# Sheet1.net
KiCad netlist of a schematic drawn in Altium Designer
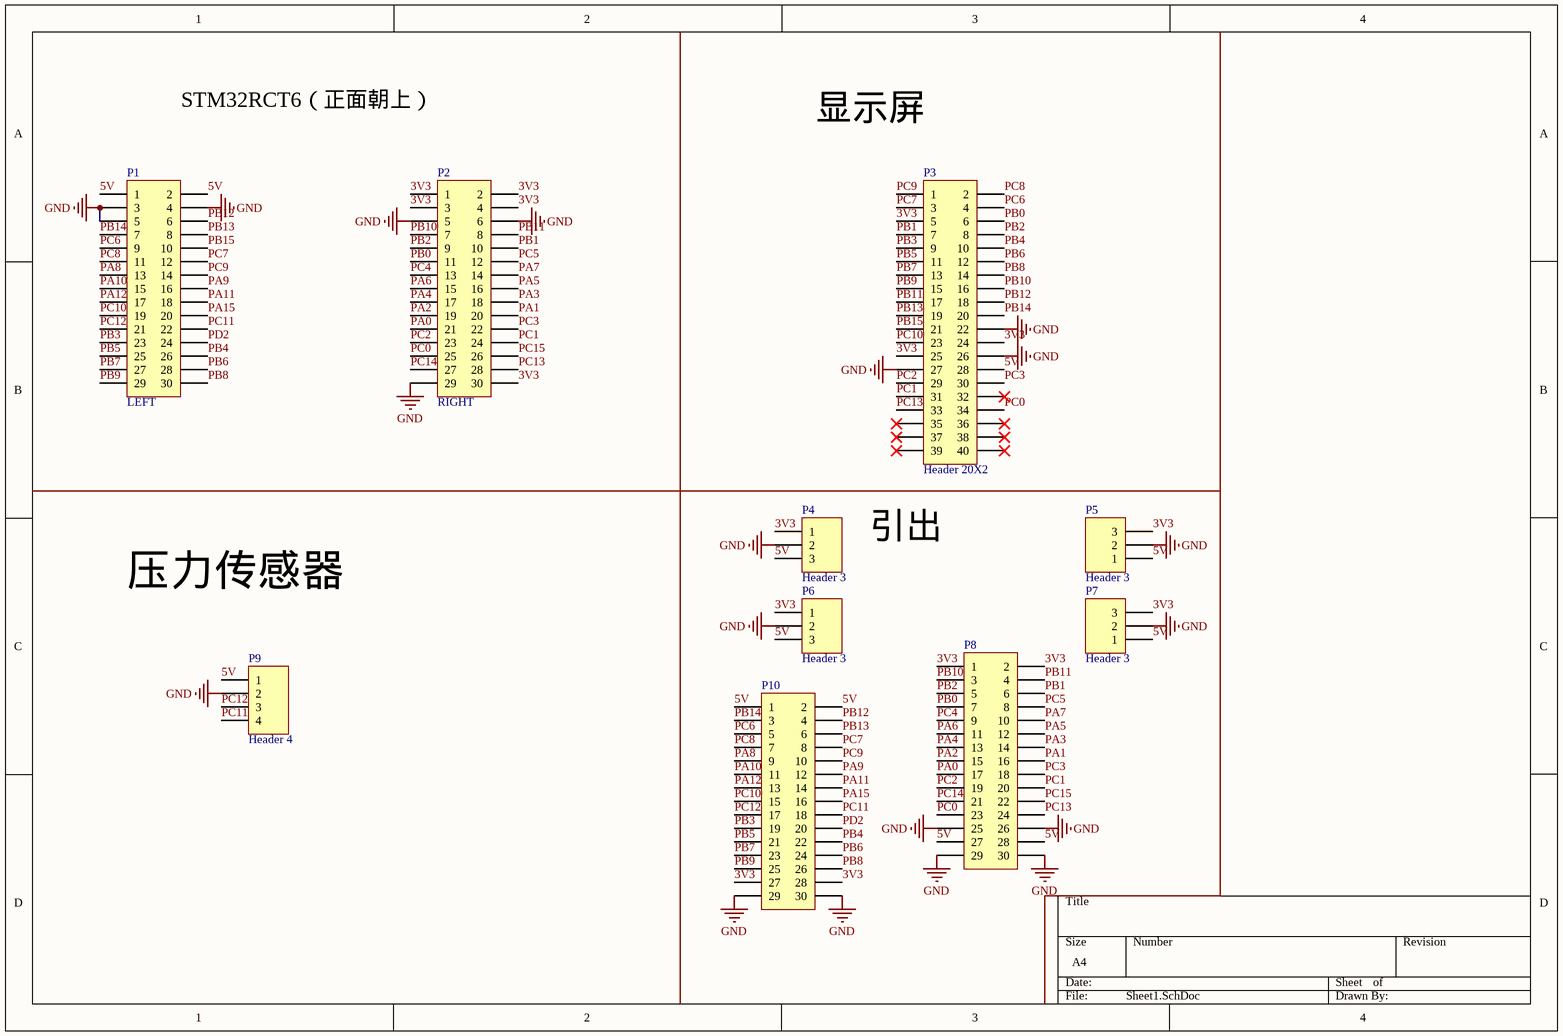
[diagram p0: Sheet1.SchDoc]

(export (version "E")
  (design (tool "Eeschema 10.0.6"))
  (components
    (comp (ref "P1")
      (value "LEFT")
      (footprint "IDE15X2_2.54")
      (description "Header, 15-Pin, Dual row")
      (fields (field (name "PUBLISHER") "Altium Limited"))
      (libsource (lib "Miscellaneous Connectors") (part "Header 15X2"))
    )
    (comp (ref "P2")
      (value "RIGHT")
      (footprint "IDE15X2_2.54")
      (description "Header, 15-Pin, Dual row")
      (fields (field (name "PUBLISHER") "Altium Limited"))
      (libsource (lib "Miscellaneous Connectors") (part "Header 15X2"))
    )
    (comp (ref "P3")
      (value "Header 20X2")
      (footprint "HDR2X20")
      (description "Header, 20-Pin, Dual row")
      (fields (field (name "PUBLISHER") "Altium Limited"))
      (libsource (lib "Miscellaneous Connectors") (part "Header 20X2"))
    )
    (comp (ref "P4")
      (value "Header 3")
      (footprint "HDR1X3")
      (description "Header, 3-Pin")
      (fields (field (name "PUBLISHER") "Altium Limited"))
      (libsource (lib "Miscellaneous Connectors") (part "Header 3"))
    )
    (comp (ref "P5")
      (value "Header 3")
      (footprint "HDR1X3")
      (description "Header, 3-Pin")
      (fields (field (name "PUBLISHER") "Altium Limited"))
      (libsource (lib "") (part "Header 3_1"))
    )
    (comp (ref "P6")
      (value "Header 3")
      (footprint "HDR1X3")
      (description "Header, 3-Pin")
      (fields (field (name "PUBLISHER") "Altium Limited"))
      (libsource (lib "Miscellaneous Connectors") (part "Header 3"))
    )
    (comp (ref "P7")
      (value "Header 3")
      (footprint "HDR1X3")
      (description "Header, 3-Pin")
      (fields (field (name "PUBLISHER") "Altium Limited"))
      (libsource (lib "") (part "Header 3_1"))
    )
    (comp (ref "P8")
      (value "~")
      (footprint "IDE15X2_2.54")
      (description "Header, 15-Pin, Dual row")
      (fields (field (name "PUBLISHER") "Altium Limited"))
      (libsource (lib "Miscellaneous Connectors") (part "Header 15X2"))
    )
    (comp (ref "P9")
      (value "Header 4")
      (footprint "HDR1X4")
      (description "Header, 4-Pin")
      (fields (field (name "PUBLISHER") "Altium Limited"))
      (libsource (lib "Miscellaneous Connectors") (part "Header 4"))
    )
    (comp (ref "P10")
      (value "~")
      (footprint "IDE15X2_2.54")
      (description "Header, 15-Pin, Dual row")
      (fields (field (name "PUBLISHER") "Altium Limited"))
      (libsource (lib "Miscellaneous Connectors") (part "Header 15X2"))
    )
  )
  (nets
    (net (code "1") (name "/3V3") (class "Default")
      (node (ref "P10") (pin "27") (pinfunction "27_27") (pintype "passive"))
      (node (ref "P10") (pin "28") (pinfunction "28_28") (pintype "passive"))
      (node (ref "P2") (pin "1") (pinfunction "1_1") (pintype "passive"))
      (node (ref "P2") (pin "2") (pinfunction "2_2") (pintype "passive"))
      (node (ref "P2") (pin "3") (pinfunction "3_3") (pintype "passive"))
      (node (ref "P2") (pin "30") (pinfunction "30_30") (pintype "passive"))
      (node (ref "P2") (pin "4") (pinfunction "4_4") (pintype "passive"))
      (node (ref "P3") (pin "24") (pinfunction "24_24") (pintype "passive"))
      (node (ref "P3") (pin "25") (pinfunction "25_25") (pintype "passive"))
      (node (ref "P3") (pin "5") (pinfunction "5_5") (pintype "passive"))
      (node (ref "P4") (pin "1") (pinfunction "1_1") (pintype "passive"))
      (node (ref "P5") (pin "3") (pinfunction "3_3") (pintype "passive"))
      (node (ref "P6") (pin "1") (pinfunction "1_1") (pintype "passive"))
      (node (ref "P7") (pin "3") (pinfunction "3_3") (pintype "passive"))
      (node (ref "P8") (pin "1") (pinfunction "1_1") (pintype "passive"))
      (node (ref "P8") (pin "2") (pinfunction "2_2") (pintype "passive"))
    )
    (net (code "2") (name "/5V") (class "Default")
      (node (ref "P1") (pin "1") (pinfunction "1_1") (pintype "passive"))
      (node (ref "P1") (pin "2") (pinfunction "2_2") (pintype "passive"))
      (node (ref "P10") (pin "1") (pinfunction "1_1") (pintype "passive"))
      (node (ref "P10") (pin "2") (pinfunction "2_2") (pintype "passive"))
      (node (ref "P3") (pin "28") (pinfunction "28_28") (pintype "passive"))
      (node (ref "P4") (pin "3") (pinfunction "3_3") (pintype "passive"))
      (node (ref "P5") (pin "1") (pinfunction "1_1") (pintype "passive"))
      (node (ref "P6") (pin "3") (pinfunction "3_3") (pintype "passive"))
      (node (ref "P7") (pin "1") (pinfunction "1_1") (pintype "passive"))
      (node (ref "P8") (pin "27") (pinfunction "27_27") (pintype "passive"))
      (node (ref "P8") (pin "28") (pinfunction "28_28") (pintype "passive"))
      (node (ref "P9") (pin "1") (pinfunction "1_1") (pintype "passive"))
    )
    (net (code "3") (name "/PA0") (class "Default")
      (node (ref "P2") (pin "21") (pinfunction "21_21") (pintype "passive"))
      (node (ref "P8") (pin "17") (pinfunction "17_17") (pintype "passive"))
    )
    (net (code "4") (name "/PA1") (class "Default")
      (node (ref "P2") (pin "20") (pinfunction "20_20") (pintype "passive"))
      (node (ref "P8") (pin "16") (pinfunction "16_16") (pintype "passive"))
    )
    (net (code "5") (name "/PA2") (class "Default")
      (node (ref "P2") (pin "19") (pinfunction "19_19") (pintype "passive"))
      (node (ref "P8") (pin "15") (pinfunction "15_15") (pintype "passive"))
    )
    (net (code "6") (name "/PA3") (class "Default")
      (node (ref "P2") (pin "18") (pinfunction "18_18") (pintype "passive"))
      (node (ref "P8") (pin "14") (pinfunction "14_14") (pintype "passive"))
    )
    (net (code "7") (name "/PA4") (class "Default")
      (node (ref "P2") (pin "17") (pinfunction "17_17") (pintype "passive"))
      (node (ref "P8") (pin "13") (pinfunction "13_13") (pintype "passive"))
    )
    (net (code "8") (name "/PA5") (class "Default")
      (node (ref "P2") (pin "16") (pinfunction "16_16") (pintype "passive"))
      (node (ref "P8") (pin "12") (pinfunction "12_12") (pintype "passive"))
    )
    (net (code "9") (name "/PA6") (class "Default")
      (node (ref "P2") (pin "15") (pinfunction "15_15") (pintype "passive"))
      (node (ref "P8") (pin "11") (pinfunction "11_11") (pintype "passive"))
    )
    (net (code "10") (name "/PA7") (class "Default")
      (node (ref "P2") (pin "14") (pinfunction "14_14") (pintype "passive"))
      (node (ref "P8") (pin "10") (pinfunction "10_10") (pintype "passive"))
    )
    (net (code "11") (name "/PA8") (class "Default")
      (node (ref "P1") (pin "13") (pinfunction "13_13") (pintype "passive"))
      (node (ref "P10") (pin "9") (pinfunction "9_9") (pintype "passive"))
    )
    (net (code "12") (name "/PA9") (class "Default")
      (node (ref "P1") (pin "16") (pinfunction "16_16") (pintype "passive"))
      (node (ref "P10") (pin "12") (pinfunction "12_12") (pintype "passive"))
    )
    (net (code "13") (name "/PA10") (class "Default")
      (node (ref "P1") (pin "15") (pinfunction "15_15") (pintype "passive"))
      (node (ref "P10") (pin "11") (pinfunction "11_11") (pintype "passive"))
    )
    (net (code "14") (name "/PA11") (class "Default")
      (node (ref "P1") (pin "18") (pinfunction "18_18") (pintype "passive"))
      (node (ref "P10") (pin "14") (pinfunction "14_14") (pintype "passive"))
    )
    (net (code "15") (name "/PA12") (class "Default")
      (node (ref "P1") (pin "17") (pinfunction "17_17") (pintype "passive"))
      (node (ref "P10") (pin "13") (pinfunction "13_13") (pintype "passive"))
    )
    (net (code "16") (name "/PA15") (class "Default")
      (node (ref "P1") (pin "20") (pinfunction "20_20") (pintype "passive"))
      (node (ref "P10") (pin "16") (pinfunction "16_16") (pintype "passive"))
    )
    (net (code "17") (name "/PB0") (class "Default")
      (node (ref "P2") (pin "11") (pinfunction "11_11") (pintype "passive"))
      (node (ref "P3") (pin "6") (pinfunction "6_6") (pintype "passive"))
      (node (ref "P8") (pin "7") (pinfunction "7_7") (pintype "passive"))
    )
    (net (code "18") (name "/PB1") (class "Default")
      (node (ref "P2") (pin "10") (pinfunction "10_10") (pintype "passive"))
      (node (ref "P3") (pin "7") (pinfunction "7_7") (pintype "passive"))
      (node (ref "P8") (pin "6") (pinfunction "6_6") (pintype "passive"))
    )
    (net (code "19") (name "/PB2") (class "Default")
      (node (ref "P2") (pin "9") (pinfunction "9_9") (pintype "passive"))
      (node (ref "P3") (pin "8") (pinfunction "8_8") (pintype "passive"))
      (node (ref "P8") (pin "5") (pinfunction "5_5") (pintype "passive"))
    )
    (net (code "20") (name "/PB3") (class "Default")
      (node (ref "P1") (pin "23") (pinfunction "23_23") (pintype "passive"))
      (node (ref "P10") (pin "19") (pinfunction "19_19") (pintype "passive"))
      (node (ref "P3") (pin "9") (pinfunction "9_9") (pintype "passive"))
    )
    (net (code "21") (name "/PB4") (class "Default")
      (node (ref "P1") (pin "26") (pinfunction "26_26") (pintype "passive"))
      (node (ref "P10") (pin "22") (pinfunction "22_22") (pintype "passive"))
      (node (ref "P3") (pin "10") (pinfunction "10_10") (pintype "passive"))
    )
    (net (code "22") (name "/PB5") (class "Default")
      (node (ref "P1") (pin "25") (pinfunction "25_25") (pintype "passive"))
      (node (ref "P10") (pin "21") (pinfunction "21_21") (pintype "passive"))
      (node (ref "P3") (pin "11") (pinfunction "11_11") (pintype "passive"))
    )
    (net (code "23") (name "/PB6") (class "Default")
      (node (ref "P1") (pin "28") (pinfunction "28_28") (pintype "passive"))
      (node (ref "P10") (pin "24") (pinfunction "24_24") (pintype "passive"))
      (node (ref "P3") (pin "12") (pinfunction "12_12") (pintype "passive"))
    )
    (net (code "24") (name "/PB7") (class "Default")
      (node (ref "P1") (pin "27") (pinfunction "27_27") (pintype "passive"))
      (node (ref "P10") (pin "23") (pinfunction "23_23") (pintype "passive"))
      (node (ref "P3") (pin "13") (pinfunction "13_13") (pintype "passive"))
    )
    (net (code "25") (name "/PB8") (class "Default")
      (node (ref "P1") (pin "30") (pinfunction "30_30") (pintype "passive"))
      (node (ref "P10") (pin "26") (pinfunction "26_26") (pintype "passive"))
      (node (ref "P3") (pin "14") (pinfunction "14_14") (pintype "passive"))
    )
    (net (code "26") (name "/PB9") (class "Default")
      (node (ref "P1") (pin "29") (pinfunction "29_29") (pintype "passive"))
      (node (ref "P10") (pin "25") (pinfunction "25_25") (pintype "passive"))
      (node (ref "P3") (pin "15") (pinfunction "15_15") (pintype "passive"))
    )
    (net (code "27") (name "/PB10") (class "Default")
      (node (ref "P2") (pin "7") (pinfunction "7_7") (pintype "passive"))
      (node (ref "P3") (pin "16") (pinfunction "16_16") (pintype "passive"))
      (node (ref "P8") (pin "3") (pinfunction "3_3") (pintype "passive"))
    )
    (net (code "28") (name "/PB11") (class "Default")
      (node (ref "P2") (pin "8") (pinfunction "8_8") (pintype "passive"))
      (node (ref "P3") (pin "17") (pinfunction "17_17") (pintype "passive"))
      (node (ref "P8") (pin "4") (pinfunction "4_4") (pintype "passive"))
    )
    (net (code "29") (name "/PB12") (class "Default")
      (node (ref "P1") (pin "6") (pinfunction "6_6") (pintype "passive"))
      (node (ref "P10") (pin "4") (pinfunction "4_4") (pintype "passive"))
      (node (ref "P3") (pin "18") (pinfunction "18_18") (pintype "passive"))
    )
    (net (code "30") (name "/PB13") (class "Default")
      (node (ref "P1") (pin "8") (pinfunction "8_8") (pintype "passive"))
      (node (ref "P10") (pin "6") (pinfunction "6_6") (pintype "passive"))
      (node (ref "P3") (pin "19") (pinfunction "19_19") (pintype "passive"))
    )
    (net (code "31") (name "/PB14") (class "Default")
      (node (ref "P1") (pin "7") (pinfunction "7_7") (pintype "passive"))
      (node (ref "P10") (pin "3") (pinfunction "3_3") (pintype "passive"))
      (node (ref "P3") (pin "20") (pinfunction "20_20") (pintype "passive"))
    )
    (net (code "32") (name "/PB15") (class "Default")
      (node (ref "P1") (pin "10") (pinfunction "10_10") (pintype "passive"))
      (node (ref "P3") (pin "21") (pinfunction "21_21") (pintype "passive"))
    )
    (net (code "33") (name "/PC0") (class "Default")
      (node (ref "P2") (pin "25") (pinfunction "25_25") (pintype "passive"))
      (node (ref "P3") (pin "34") (pinfunction "34_34") (pintype "passive"))
      (node (ref "P8") (pin "23") (pinfunction "23_23") (pintype "passive"))
    )
    (net (code "34") (name "/PC1") (class "Default")
      (node (ref "P2") (pin "24") (pinfunction "24_24") (pintype "passive"))
      (node (ref "P3") (pin "31") (pinfunction "31_31") (pintype "passive"))
      (node (ref "P8") (pin "20") (pinfunction "20_20") (pintype "passive"))
    )
    (net (code "35") (name "/PC2") (class "Default")
      (node (ref "P2") (pin "23") (pinfunction "23_23") (pintype "passive"))
      (node (ref "P3") (pin "29") (pinfunction "29_29") (pintype "passive"))
      (node (ref "P8") (pin "19") (pinfunction "19_19") (pintype "passive"))
    )
    (net (code "36") (name "/PC3") (class "Default")
      (node (ref "P2") (pin "22") (pinfunction "22_22") (pintype "passive"))
      (node (ref "P3") (pin "30") (pinfunction "30_30") (pintype "passive"))
      (node (ref "P8") (pin "18") (pinfunction "18_18") (pintype "passive"))
    )
    (net (code "37") (name "/PC4") (class "Default")
      (node (ref "P2") (pin "13") (pinfunction "13_13") (pintype "passive"))
      (node (ref "P8") (pin "9") (pinfunction "9_9") (pintype "passive"))
    )
    (net (code "38") (name "/PC5") (class "Default")
      (node (ref "P2") (pin "12") (pinfunction "12_12") (pintype "passive"))
      (node (ref "P8") (pin "8") (pinfunction "8_8") (pintype "passive"))
    )
    (net (code "39") (name "/PC6") (class "Default")
      (node (ref "P1") (pin "9") (pinfunction "9_9") (pintype "passive"))
      (node (ref "P10") (pin "5") (pinfunction "5_5") (pintype "passive"))
      (node (ref "P3") (pin "4") (pinfunction "4_4") (pintype "passive"))
    )
    (net (code "40") (name "/PC7") (class "Default")
      (node (ref "P1") (pin "12") (pinfunction "12_12") (pintype "passive"))
      (node (ref "P10") (pin "8") (pinfunction "8_8") (pintype "passive"))
      (node (ref "P3") (pin "3") (pinfunction "3_3") (pintype "passive"))
    )
    (net (code "41") (name "/PC8") (class "Default")
      (node (ref "P1") (pin "11") (pinfunction "11_11") (pintype "passive"))
      (node (ref "P10") (pin "7") (pinfunction "7_7") (pintype "passive"))
      (node (ref "P3") (pin "2") (pinfunction "2_2") (pintype "passive"))
    )
    (net (code "42") (name "/PC9") (class "Default")
      (node (ref "P1") (pin "14") (pinfunction "14_14") (pintype "passive"))
      (node (ref "P10") (pin "10") (pinfunction "10_10") (pintype "passive"))
      (node (ref "P3") (pin "1") (pinfunction "1_1") (pintype "passive"))
    )
    (net (code "43") (name "/PC10") (class "Default")
      (node (ref "P1") (pin "19") (pinfunction "19_19") (pintype "passive"))
      (node (ref "P10") (pin "15") (pinfunction "15_15") (pintype "passive"))
      (node (ref "P3") (pin "23") (pinfunction "23_23") (pintype "passive"))
    )
    (net (code "44") (name "/PC11") (class "Default")
      (node (ref "P1") (pin "22") (pinfunction "22_22") (pintype "passive"))
      (node (ref "P10") (pin "18") (pinfunction "18_18") (pintype "passive"))
      (node (ref "P9") (pin "4") (pinfunction "4_4") (pintype "passive"))
    )
    (net (code "45") (name "/PC12") (class "Default")
      (node (ref "P1") (pin "21") (pinfunction "21_21") (pintype "passive"))
      (node (ref "P10") (pin "17") (pinfunction "17_17") (pintype "passive"))
      (node (ref "P9") (pin "3") (pinfunction "3_3") (pintype "passive"))
    )
    (net (code "46") (name "/PC13") (class "Default")
      (node (ref "P2") (pin "28") (pinfunction "28_28") (pintype "passive"))
      (node (ref "P3") (pin "33") (pinfunction "33_33") (pintype "passive"))
      (node (ref "P8") (pin "24") (pinfunction "24_24") (pintype "passive"))
    )
    (net (code "47") (name "/PC14") (class "Default")
      (node (ref "P2") (pin "27") (pinfunction "27_27") (pintype "passive"))
      (node (ref "P8") (pin "21") (pinfunction "21_21") (pintype "passive"))
    )
    (net (code "48") (name "/PC15") (class "Default")
      (node (ref "P2") (pin "26") (pinfunction "26_26") (pintype "passive"))
      (node (ref "P8") (pin "22") (pinfunction "22_22") (pintype "passive"))
    )
    (net (code "49") (name "/PD2") (class "Default")
      (node (ref "P1") (pin "24") (pinfunction "24_24") (pintype "passive"))
      (node (ref "P10") (pin "20") (pinfunction "20_20") (pintype "passive"))
    )
    (net (code "50") (name "GND") (class "Default")
      (node (ref "P1") (pin "3") (pinfunction "3_3") (pintype "passive"))
      (node (ref "P1") (pin "4") (pinfunction "4_4") (pintype "passive"))
      (node (ref "P1") (pin "5") (pinfunction "5_5") (pintype "passive"))
      (node (ref "P10") (pin "29") (pinfunction "29_29") (pintype "passive"))
      (node (ref "P10") (pin "30") (pinfunction "30_30") (pintype "passive"))
      (node (ref "P2") (pin "29") (pinfunction "29_29") (pintype "passive"))
      (node (ref "P2") (pin "5") (pinfunction "5_5") (pintype "passive"))
      (node (ref "P2") (pin "6") (pinfunction "6_6") (pintype "passive"))
      (node (ref "P3") (pin "22") (pinfunction "22_22") (pintype "passive"))
      (node (ref "P3") (pin "26") (pinfunction "26_26") (pintype "passive"))
      (node (ref "P3") (pin "27") (pinfunction "27_27") (pintype "passive"))
      (node (ref "P4") (pin "2") (pinfunction "2_2") (pintype "passive"))
      (node (ref "P5") (pin "2") (pinfunction "2_2") (pintype "passive"))
      (node (ref "P6") (pin "2") (pinfunction "2_2") (pintype "passive"))
      (node (ref "P7") (pin "2") (pinfunction "2_2") (pintype "passive"))
      (node (ref "P8") (pin "25") (pinfunction "25_25") (pintype "passive"))
      (node (ref "P8") (pin "26") (pinfunction "26_26") (pintype "passive"))
      (node (ref "P8") (pin "29") (pinfunction "29_29") (pintype "passive"))
      (node (ref "P8") (pin "30") (pinfunction "30_30") (pintype "passive"))
      (node (ref "P9") (pin "2") (pinfunction "2_2") (pintype "passive"))
    )
    (net (code "51") (name "unconnected-(P3-Pad32)") (class "Default")
      (node (ref "P3") (pin "32") (pinfunction "32_32") (pintype "passive+no_connect"))
    )
    (net (code "52") (name "unconnected-(P3-Pad35)") (class "Default")
      (node (ref "P3") (pin "35") (pinfunction "35_35") (pintype "passive+no_connect"))
    )
    (net (code "53") (name "unconnected-(P3-Pad36)") (class "Default")
      (node (ref "P3") (pin "36") (pinfunction "36_36") (pintype "passive+no_connect"))
    )
    (net (code "54") (name "unconnected-(P3-Pad37)") (class "Default")
      (node (ref "P3") (pin "37") (pinfunction "37_37") (pintype "passive+no_connect"))
    )
    (net (code "55") (name "unconnected-(P3-Pad38)") (class "Default")
      (node (ref "P3") (pin "38") (pinfunction "38_38") (pintype "passive+no_connect"))
    )
    (net (code "56") (name "unconnected-(P3-Pad39)") (class "Default")
      (node (ref "P3") (pin "39") (pinfunction "39_39") (pintype "passive+no_connect"))
    )
    (net (code "57") (name "unconnected-(P3-Pad40)") (class "Default")
      (node (ref "P3") (pin "40") (pinfunction "40_40") (pintype "passive+no_connect"))
    )
  )
)
